# design.net
KiCad netlist of a schematic drawn in EAGLE
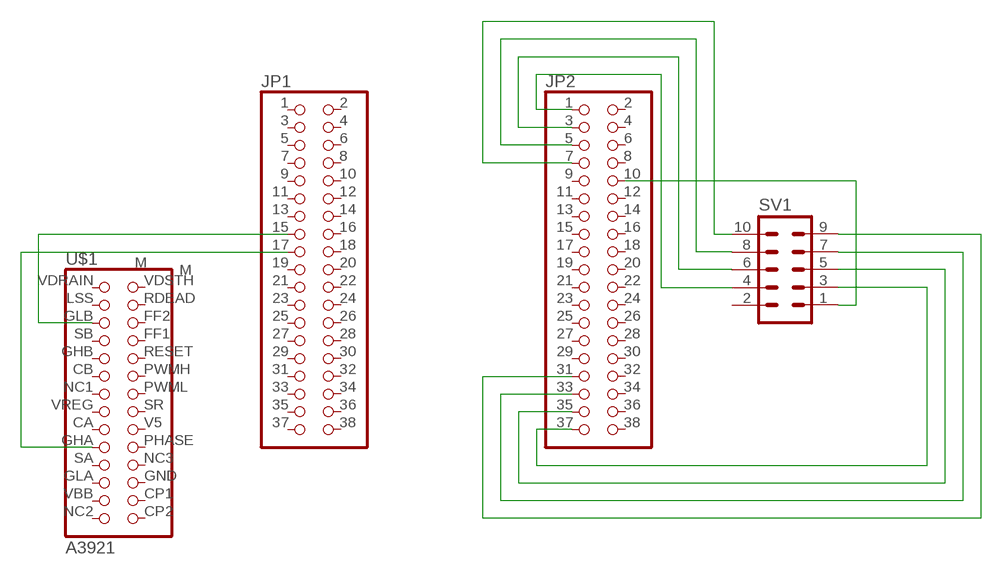
[diagram p0: schematic, sheet 1]

(export (version "E")
  (design (tool "Eeschema 10.0.6"))
  (components
    (comp (ref "JP1")
      (value "PINHD-2X19")
      (footprint "eagle-import:2X19")
      (libsource (lib "eagle-import") (part "PINHD-2X19"))
    )
    (comp (ref "JP2")
      (value "PINHD-2X19")
      (footprint "eagle-import:2X19")
      (libsource (lib "eagle-import") (part "PINHD-2X19"))
    )
    (comp (ref "SV1")
      (value "ML10L")
      (footprint "eagle-import:ML10L")
      (libsource (lib "eagle-import") (part "ML10L"))
    )
    (comp (ref "U$1")
      (value "A3921")
      (footprint "eagle-import:A3921")
      (libsource (lib "eagle-import") (part "A3921"))
    )
  )
  (nets
    (net (code "1") (name "Net-(JP1-Pad15)") (class "Default")
      (node (ref "JP1") (pin "15") (pinfunction "15_15") (pintype "passive"))
      (node (ref "U$1") (pin "GLB") (pinfunction "GLB_GLB") (pintype "passive"))
    )
    (net (code "2") (name "Net-(JP1-Pad17)") (class "Default")
      (node (ref "JP1") (pin "17") (pinfunction "17_17") (pintype "passive"))
      (node (ref "U$1") (pin "GHA") (pinfunction "GHA_GHA") (pintype "passive"))
    )
    (net (code "3") (name "Net-(JP2-Pad1)") (class "Default")
      (node (ref "JP2") (pin "1") (pinfunction "1_1") (pintype "passive"))
      (node (ref "SV1") (pin "4") (pinfunction "4_4") (pintype "passive"))
    )
    (net (code "4") (name "Net-(JP2-Pad3)") (class "Default")
      (node (ref "JP2") (pin "3") (pinfunction "3_3") (pintype "passive"))
      (node (ref "SV1") (pin "6") (pinfunction "6_6") (pintype "passive"))
    )
    (net (code "5") (name "Net-(JP2-Pad5)") (class "Default")
      (node (ref "JP2") (pin "5") (pinfunction "5_5") (pintype "passive"))
      (node (ref "SV1") (pin "8") (pinfunction "8_8") (pintype "passive"))
    )
    (net (code "6") (name "Net-(JP2-Pad7)") (class "Default")
      (node (ref "JP2") (pin "7") (pinfunction "7_7") (pintype "passive"))
      (node (ref "SV1") (pin "10") (pinfunction "10_10") (pintype "passive"))
    )
    (net (code "7") (name "Net-(JP2-Pad10)") (class "Default")
      (node (ref "JP2") (pin "10") (pinfunction "10_10") (pintype "passive"))
      (node (ref "SV1") (pin "1") (pinfunction "1_1") (pintype "passive"))
    )
    (net (code "8") (name "Net-(JP2-Pad31)") (class "Default")
      (node (ref "JP2") (pin "31") (pinfunction "31_31") (pintype "passive"))
      (node (ref "SV1") (pin "9") (pinfunction "9_9") (pintype "passive"))
    )
    (net (code "9") (name "Net-(JP2-Pad33)") (class "Default")
      (node (ref "JP2") (pin "33") (pinfunction "33_33") (pintype "passive"))
      (node (ref "SV1") (pin "7") (pinfunction "7_7") (pintype "passive"))
    )
    (net (code "10") (name "Net-(JP2-Pad35)") (class "Default")
      (node (ref "JP2") (pin "35") (pinfunction "35_35") (pintype "passive"))
      (node (ref "SV1") (pin "5") (pinfunction "5_5") (pintype "passive"))
    )
    (net (code "11") (name "Net-(JP2-Pad37)") (class "Default")
      (node (ref "JP2") (pin "37") (pinfunction "37_37") (pintype "passive"))
      (node (ref "SV1") (pin "3") (pinfunction "3_3") (pintype "passive"))
    )
    (net (code "12") (name "unconnected-(JP1-Pad1)") (class "Default")
      (node (ref "JP1") (pin "1") (pinfunction "1_1") (pintype "passive"))
    )
    (net (code "13") (name "unconnected-(JP1-Pad2)") (class "Default")
      (node (ref "JP1") (pin "2") (pinfunction "2_2") (pintype "passive"))
    )
    (net (code "14") (name "unconnected-(JP1-Pad3)") (class "Default")
      (node (ref "JP1") (pin "3") (pinfunction "3_3") (pintype "passive"))
    )
    (net (code "15") (name "unconnected-(JP1-Pad4)") (class "Default")
      (node (ref "JP1") (pin "4") (pinfunction "4_4") (pintype "passive"))
    )
    (net (code "16") (name "unconnected-(JP1-Pad5)") (class "Default")
      (node (ref "JP1") (pin "5") (pinfunction "5_5") (pintype "passive"))
    )
    (net (code "17") (name "unconnected-(JP1-Pad6)") (class "Default")
      (node (ref "JP1") (pin "6") (pinfunction "6_6") (pintype "passive"))
    )
    (net (code "18") (name "unconnected-(JP1-Pad7)") (class "Default")
      (node (ref "JP1") (pin "7") (pinfunction "7_7") (pintype "passive"))
    )
    (net (code "19") (name "unconnected-(JP1-Pad8)") (class "Default")
      (node (ref "JP1") (pin "8") (pinfunction "8_8") (pintype "passive"))
    )
    (net (code "20") (name "unconnected-(JP1-Pad9)") (class "Default")
      (node (ref "JP1") (pin "9") (pinfunction "9_9") (pintype "passive"))
    )
    (net (code "21") (name "unconnected-(JP1-Pad10)") (class "Default")
      (node (ref "JP1") (pin "10") (pinfunction "10_10") (pintype "passive"))
    )
    (net (code "22") (name "unconnected-(JP1-Pad11)") (class "Default")
      (node (ref "JP1") (pin "11") (pinfunction "11_11") (pintype "passive"))
    )
    (net (code "23") (name "unconnected-(JP1-Pad12)") (class "Default")
      (node (ref "JP1") (pin "12") (pinfunction "12_12") (pintype "passive"))
    )
    (net (code "24") (name "unconnected-(JP1-Pad13)") (class "Default")
      (node (ref "JP1") (pin "13") (pinfunction "13_13") (pintype "passive"))
    )
    (net (code "25") (name "unconnected-(JP1-Pad14)") (class "Default")
      (node (ref "JP1") (pin "14") (pinfunction "14_14") (pintype "passive"))
    )
    (net (code "26") (name "unconnected-(JP1-Pad16)") (class "Default")
      (node (ref "JP1") (pin "16") (pinfunction "16_16") (pintype "passive"))
    )
    (net (code "27") (name "unconnected-(JP1-Pad18)") (class "Default")
      (node (ref "JP1") (pin "18") (pinfunction "18_18") (pintype "passive"))
    )
    (net (code "28") (name "unconnected-(JP1-Pad19)") (class "Default")
      (node (ref "JP1") (pin "19") (pinfunction "19_19") (pintype "passive"))
    )
    (net (code "29") (name "unconnected-(JP1-Pad20)") (class "Default")
      (node (ref "JP1") (pin "20") (pinfunction "20_20") (pintype "passive"))
    )
    (net (code "30") (name "unconnected-(JP1-Pad21)") (class "Default")
      (node (ref "JP1") (pin "21") (pinfunction "21_21") (pintype "passive"))
    )
    (net (code "31") (name "unconnected-(JP1-Pad22)") (class "Default")
      (node (ref "JP1") (pin "22") (pinfunction "22_22") (pintype "passive"))
    )
    (net (code "32") (name "unconnected-(JP1-Pad23)") (class "Default")
      (node (ref "JP1") (pin "23") (pinfunction "23_23") (pintype "passive"))
    )
    (net (code "33") (name "unconnected-(JP1-Pad24)") (class "Default")
      (node (ref "JP1") (pin "24") (pinfunction "24_24") (pintype "passive"))
    )
    (net (code "34") (name "unconnected-(JP1-Pad25)") (class "Default")
      (node (ref "JP1") (pin "25") (pinfunction "25_25") (pintype "passive"))
    )
    (net (code "35") (name "unconnected-(JP1-Pad26)") (class "Default")
      (node (ref "JP1") (pin "26") (pinfunction "26_26") (pintype "passive"))
    )
    (net (code "36") (name "unconnected-(JP1-Pad27)") (class "Default")
      (node (ref "JP1") (pin "27") (pinfunction "27_27") (pintype "passive"))
    )
    (net (code "37") (name "unconnected-(JP1-Pad28)") (class "Default")
      (node (ref "JP1") (pin "28") (pinfunction "28_28") (pintype "passive"))
    )
    (net (code "38") (name "unconnected-(JP1-Pad29)") (class "Default")
      (node (ref "JP1") (pin "29") (pinfunction "29_29") (pintype "passive"))
    )
    (net (code "39") (name "unconnected-(JP1-Pad30)") (class "Default")
      (node (ref "JP1") (pin "30") (pinfunction "30_30") (pintype "passive"))
    )
    (net (code "40") (name "unconnected-(JP1-Pad31)") (class "Default")
      (node (ref "JP1") (pin "31") (pinfunction "31_31") (pintype "passive"))
    )
    (net (code "41") (name "unconnected-(JP1-Pad32)") (class "Default")
      (node (ref "JP1") (pin "32") (pinfunction "32_32") (pintype "passive"))
    )
    (net (code "42") (name "unconnected-(JP1-Pad33)") (class "Default")
      (node (ref "JP1") (pin "33") (pinfunction "33_33") (pintype "passive"))
    )
    (net (code "43") (name "unconnected-(JP1-Pad34)") (class "Default")
      (node (ref "JP1") (pin "34") (pinfunction "34_34") (pintype "passive"))
    )
    (net (code "44") (name "unconnected-(JP1-Pad35)") (class "Default")
      (node (ref "JP1") (pin "35") (pinfunction "35_35") (pintype "passive"))
    )
    (net (code "45") (name "unconnected-(JP1-Pad36)") (class "Default")
      (node (ref "JP1") (pin "36") (pinfunction "36_36") (pintype "passive"))
    )
    (net (code "46") (name "unconnected-(JP1-Pad37)") (class "Default")
      (node (ref "JP1") (pin "37") (pinfunction "37_37") (pintype "passive"))
    )
    (net (code "47") (name "unconnected-(JP1-Pad38)") (class "Default")
      (node (ref "JP1") (pin "38") (pinfunction "38_38") (pintype "passive"))
    )
    (net (code "48") (name "unconnected-(JP2-Pad2)") (class "Default")
      (node (ref "JP2") (pin "2") (pinfunction "2_2") (pintype "passive"))
    )
    (net (code "49") (name "unconnected-(JP2-Pad4)") (class "Default")
      (node (ref "JP2") (pin "4") (pinfunction "4_4") (pintype "passive"))
    )
    (net (code "50") (name "unconnected-(JP2-Pad6)") (class "Default")
      (node (ref "JP2") (pin "6") (pinfunction "6_6") (pintype "passive"))
    )
    (net (code "51") (name "unconnected-(JP2-Pad8)") (class "Default")
      (node (ref "JP2") (pin "8") (pinfunction "8_8") (pintype "passive"))
    )
    (net (code "52") (name "unconnected-(JP2-Pad9)") (class "Default")
      (node (ref "JP2") (pin "9") (pinfunction "9_9") (pintype "passive"))
    )
    (net (code "53") (name "unconnected-(JP2-Pad11)") (class "Default")
      (node (ref "JP2") (pin "11") (pinfunction "11_11") (pintype "passive"))
    )
    (net (code "54") (name "unconnected-(JP2-Pad12)") (class "Default")
      (node (ref "JP2") (pin "12") (pinfunction "12_12") (pintype "passive"))
    )
    (net (code "55") (name "unconnected-(JP2-Pad13)") (class "Default")
      (node (ref "JP2") (pin "13") (pinfunction "13_13") (pintype "passive"))
    )
    (net (code "56") (name "unconnected-(JP2-Pad14)") (class "Default")
      (node (ref "JP2") (pin "14") (pinfunction "14_14") (pintype "passive"))
    )
    (net (code "57") (name "unconnected-(JP2-Pad15)") (class "Default")
      (node (ref "JP2") (pin "15") (pinfunction "15_15") (pintype "passive"))
    )
    (net (code "58") (name "unconnected-(JP2-Pad16)") (class "Default")
      (node (ref "JP2") (pin "16") (pinfunction "16_16") (pintype "passive"))
    )
    (net (code "59") (name "unconnected-(JP2-Pad17)") (class "Default")
      (node (ref "JP2") (pin "17") (pinfunction "17_17") (pintype "passive"))
    )
    (net (code "60") (name "unconnected-(JP2-Pad18)") (class "Default")
      (node (ref "JP2") (pin "18") (pinfunction "18_18") (pintype "passive"))
    )
    (net (code "61") (name "unconnected-(JP2-Pad19)") (class "Default")
      (node (ref "JP2") (pin "19") (pinfunction "19_19") (pintype "passive"))
    )
    (net (code "62") (name "unconnected-(JP2-Pad20)") (class "Default")
      (node (ref "JP2") (pin "20") (pinfunction "20_20") (pintype "passive"))
    )
    (net (code "63") (name "unconnected-(JP2-Pad21)") (class "Default")
      (node (ref "JP2") (pin "21") (pinfunction "21_21") (pintype "passive"))
    )
    (net (code "64") (name "unconnected-(JP2-Pad22)") (class "Default")
      (node (ref "JP2") (pin "22") (pinfunction "22_22") (pintype "passive"))
    )
    (net (code "65") (name "unconnected-(JP2-Pad23)") (class "Default")
      (node (ref "JP2") (pin "23") (pinfunction "23_23") (pintype "passive"))
    )
    (net (code "66") (name "unconnected-(JP2-Pad24)") (class "Default")
      (node (ref "JP2") (pin "24") (pinfunction "24_24") (pintype "passive"))
    )
    (net (code "67") (name "unconnected-(JP2-Pad25)") (class "Default")
      (node (ref "JP2") (pin "25") (pinfunction "25_25") (pintype "passive"))
    )
    (net (code "68") (name "unconnected-(JP2-Pad26)") (class "Default")
      (node (ref "JP2") (pin "26") (pinfunction "26_26") (pintype "passive"))
    )
    (net (code "69") (name "unconnected-(JP2-Pad27)") (class "Default")
      (node (ref "JP2") (pin "27") (pinfunction "27_27") (pintype "passive"))
    )
    (net (code "70") (name "unconnected-(JP2-Pad28)") (class "Default")
      (node (ref "JP2") (pin "28") (pinfunction "28_28") (pintype "passive"))
    )
    (net (code "71") (name "unconnected-(JP2-Pad29)") (class "Default")
      (node (ref "JP2") (pin "29") (pinfunction "29_29") (pintype "passive"))
    )
    (net (code "72") (name "unconnected-(JP2-Pad30)") (class "Default")
      (node (ref "JP2") (pin "30") (pinfunction "30_30") (pintype "passive"))
    )
    (net (code "73") (name "unconnected-(JP2-Pad32)") (class "Default")
      (node (ref "JP2") (pin "32") (pinfunction "32_32") (pintype "passive"))
    )
    (net (code "74") (name "unconnected-(JP2-Pad34)") (class "Default")
      (node (ref "JP2") (pin "34") (pinfunction "34_34") (pintype "passive"))
    )
    (net (code "75") (name "unconnected-(JP2-Pad36)") (class "Default")
      (node (ref "JP2") (pin "36") (pinfunction "36_36") (pintype "passive"))
    )
    (net (code "76") (name "unconnected-(JP2-Pad38)") (class "Default")
      (node (ref "JP2") (pin "38") (pinfunction "38_38") (pintype "passive"))
    )
    (net (code "77") (name "unconnected-(SV1-Pad2)") (class "Default")
      (node (ref "SV1") (pin "2") (pinfunction "2_2") (pintype "passive"))
    )
    (net (code "78") (name "unconnected-(U$1-PadCA)") (class "Default")
      (node (ref "U$1") (pin "CA") (pinfunction "CA_CA") (pintype "passive"))
    )
    (net (code "79") (name "unconnected-(U$1-PadCB)") (class "Default")
      (node (ref "U$1") (pin "CB") (pinfunction "CB_CB") (pintype "passive"))
    )
    (net (code "80") (name "unconnected-(U$1-PadCP1)") (class "Default")
      (node (ref "U$1") (pin "CP1") (pinfunction "CP1_CP1") (pintype "passive"))
    )
    (net (code "81") (name "unconnected-(U$1-PadCP2)") (class "Default")
      (node (ref "U$1") (pin "CP2") (pinfunction "CP2_CP2") (pintype "passive"))
    )
    (net (code "82") (name "unconnected-(U$1-PadFF1)") (class "Default")
      (node (ref "U$1") (pin "FF1") (pinfunction "FF1_FF1") (pintype "passive"))
    )
    (net (code "83") (name "unconnected-(U$1-PadFF2)") (class "Default")
      (node (ref "U$1") (pin "FF2") (pinfunction "FF2_FF2") (pintype "passive"))
    )
    (net (code "84") (name "unconnected-(U$1-PadGHB)") (class "Default")
      (node (ref "U$1") (pin "GHB") (pinfunction "GHB_GHB") (pintype "passive"))
    )
    (net (code "85") (name "unconnected-(U$1-PadGLA)") (class "Default")
      (node (ref "U$1") (pin "GLA") (pinfunction "GLA_GLA") (pintype "passive"))
    )
    (net (code "86") (name "unconnected-(U$1-PadGND)") (class "Default")
      (node (ref "U$1") (pin "GND") (pinfunction "GND_GND") (pintype "passive"))
    )
    (net (code "87") (name "unconnected-(U$1-PadLSS)") (class "Default")
      (node (ref "U$1") (pin "LSS") (pinfunction "LSS_LSS") (pintype "passive"))
    )
    (net (code "88") (name "unconnected-(U$1-PadM)") (class "Default")
      (node (ref "U$1") (pin "M") (pinfunction "M_M") (pintype "bidirectional"))
    )
    (net (code "89") (name "unconnected-(U$1-PadNC1)") (class "Default")
      (node (ref "U$1") (pin "NC1") (pinfunction "NC1_NC1") (pintype "passive"))
    )
    (net (code "90") (name "unconnected-(U$1-PadNC2)") (class "Default")
      (node (ref "U$1") (pin "NC2") (pinfunction "NC2_NC2") (pintype "passive"))
    )
    (net (code "91") (name "unconnected-(U$1-PadNC3)") (class "Default")
      (node (ref "U$1") (pin "NC3") (pinfunction "NC3_NC3") (pintype "passive"))
    )
    (net (code "92") (name "unconnected-(U$1-PadPHASE)") (class "Default")
      (node (ref "U$1") (pin "PHASE") (pinfunction "PHASE_PHASE") (pintype "passive"))
    )
    (net (code "93") (name "unconnected-(U$1-PadPWMH)") (class "Default")
      (node (ref "U$1") (pin "PWMH") (pinfunction "PWMH_PWMH") (pintype "passive"))
    )
    (net (code "94") (name "unconnected-(U$1-PadPWML)") (class "Default")
      (node (ref "U$1") (pin "PWML") (pinfunction "PWML_PWML") (pintype "passive"))
    )
    (net (code "95") (name "unconnected-(U$1-PadRDEAD)") (class "Default")
      (node (ref "U$1") (pin "RDEAD") (pinfunction "RDEAD_RDEAD") (pintype "passive"))
    )
    (net (code "96") (name "unconnected-(U$1-PadRESET)") (class "Default")
      (node (ref "U$1") (pin "RESET") (pinfunction "RESET_RESET") (pintype "passive"))
    )
    (net (code "97") (name "unconnected-(U$1-PadSA)") (class "Default")
      (node (ref "U$1") (pin "SA") (pinfunction "SA_SA") (pintype "passive"))
    )
    (net (code "98") (name "unconnected-(U$1-PadSB)") (class "Default")
      (node (ref "U$1") (pin "SB") (pinfunction "SB_SB") (pintype "passive"))
    )
    (net (code "99") (name "unconnected-(U$1-PadSR)") (class "Default")
      (node (ref "U$1") (pin "SR") (pinfunction "SR_SR") (pintype "passive"))
    )
    (net (code "100") (name "unconnected-(U$1-PadV5)") (class "Default")
      (node (ref "U$1") (pin "V5") (pinfunction "V5_V5") (pintype "passive"))
    )
    (net (code "101") (name "unconnected-(U$1-PadVBB)") (class "Default")
      (node (ref "U$1") (pin "VBB") (pinfunction "VBB_VBB") (pintype "passive"))
    )
    (net (code "102") (name "unconnected-(U$1-PadVDRAIN)") (class "Default")
      (node (ref "U$1") (pin "VDRAIN") (pinfunction "VDRAIN_VDRAIN") (pintype "passive"))
    )
    (net (code "103") (name "unconnected-(U$1-PadVDSTH)") (class "Default")
      (node (ref "U$1") (pin "VDSTH") (pinfunction "VDSTH_VDSTH") (pintype "passive"))
    )
    (net (code "104") (name "unconnected-(U$1-PadVREG)") (class "Default")
      (node (ref "U$1") (pin "VREG") (pinfunction "VREG_VREG") (pintype "passive"))
    )
  )
)
